# yacc2buss.net
KiCad netlist of a schematic drawn in EAGLE
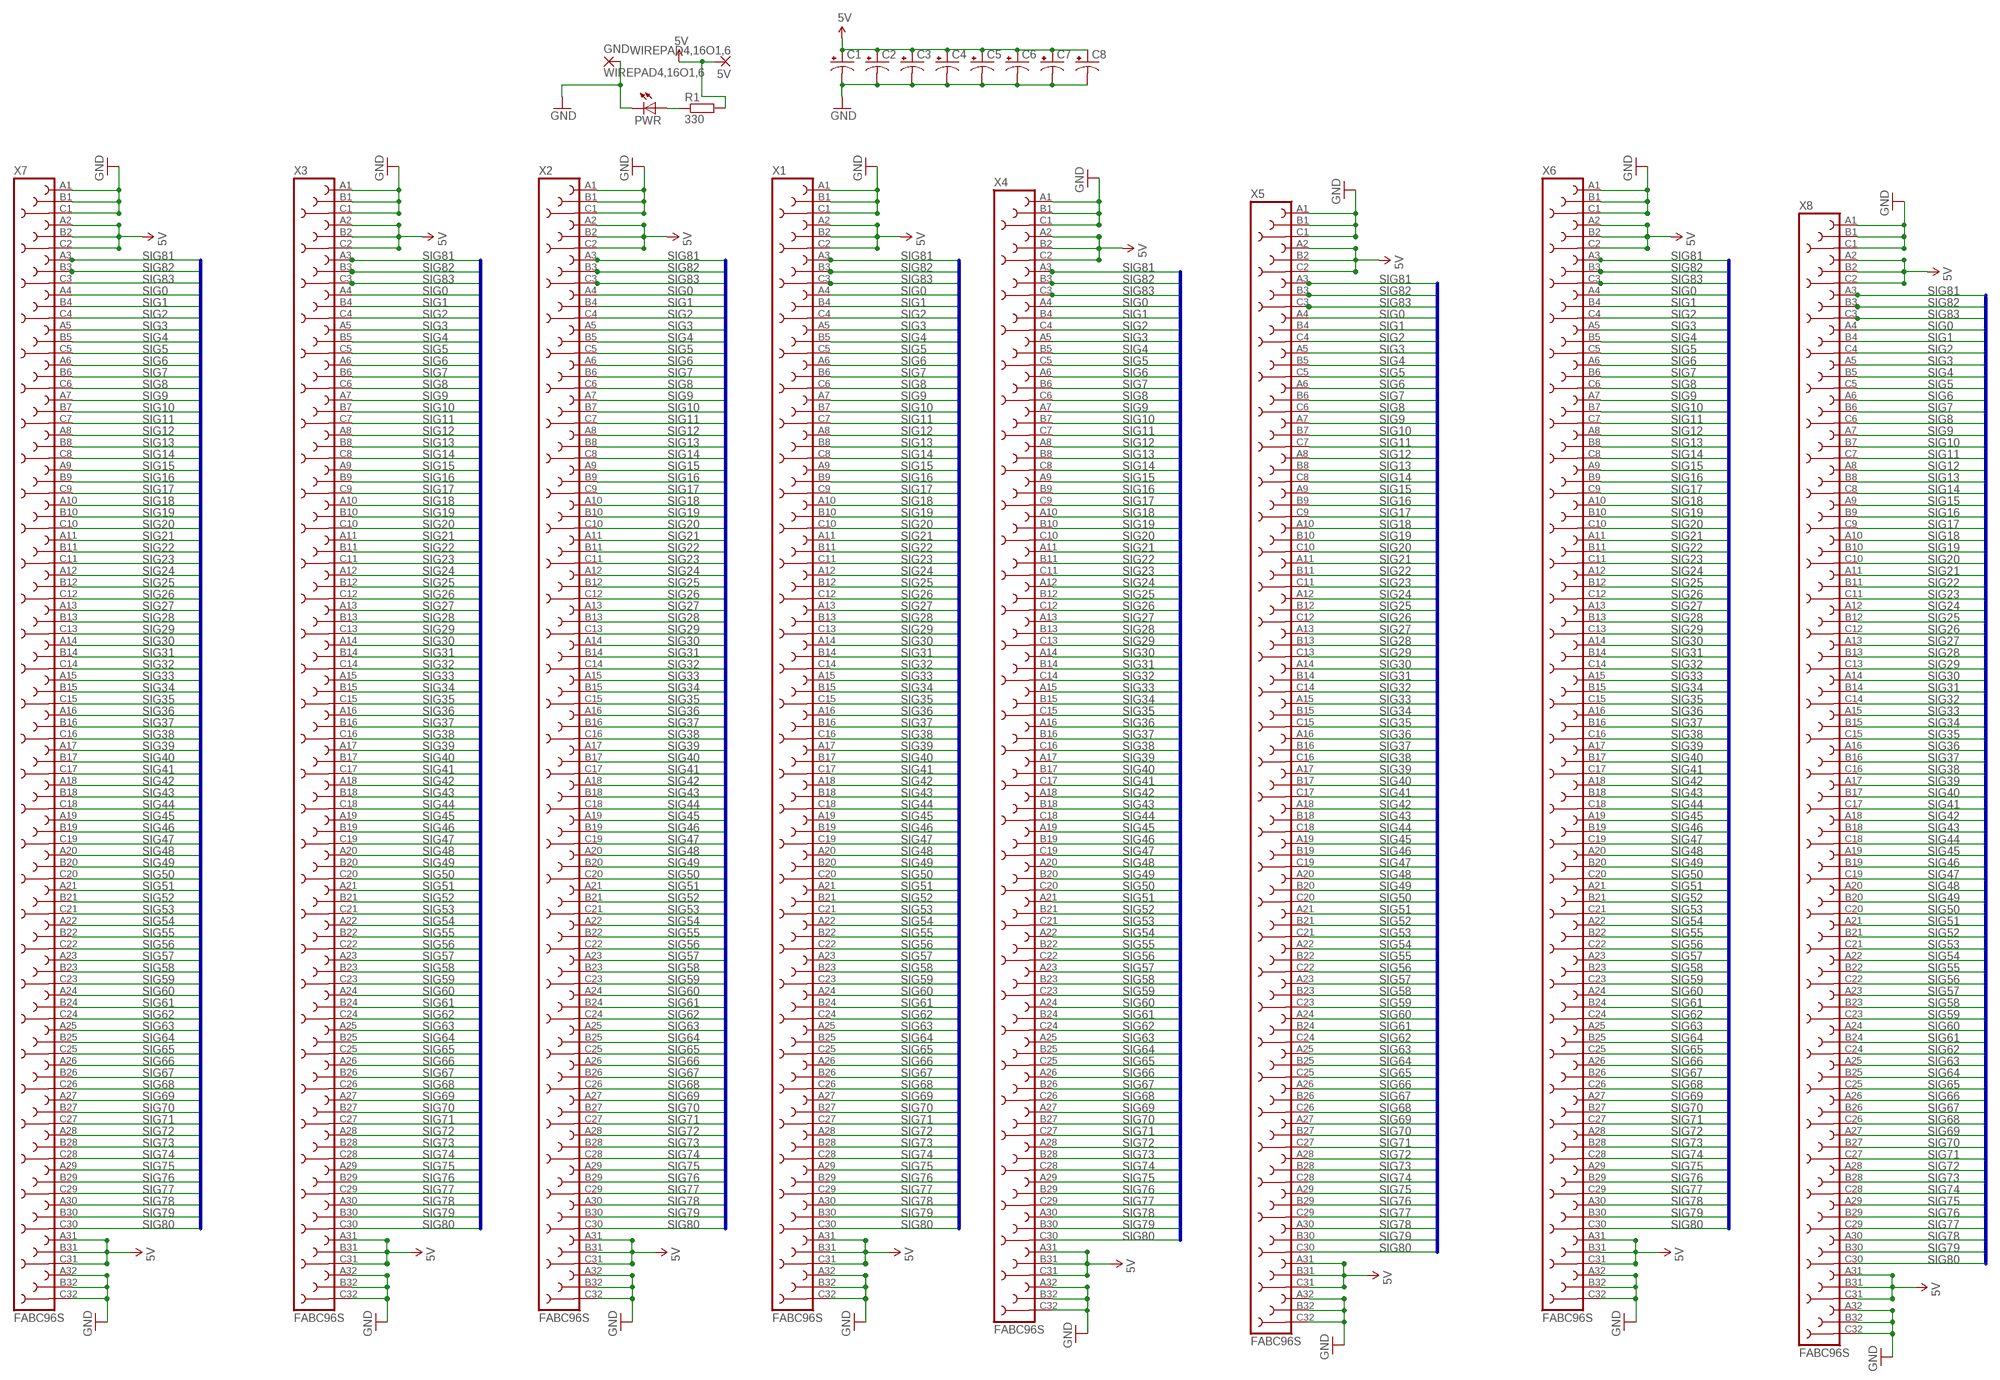
[diagram p0: schematic, sheet 1]

(export (version "E")
  (design (tool "Eeschema 10.0.6"))
  (components
    (comp (ref "5V")
      (value "WIREPAD4,16O1,6")
      (footprint "eagle-import:4,16O1,6")
      (libsource (lib "eagle-import") (part "WIREPAD4,16O1,6"))
    )
    (comp (ref "C1")
      (value "CPOL-USE5-6")
      (footprint "eagle-import:E5-6")
      (libsource (lib "eagle-import") (part "CPOL-USE5-6"))
    )
    (comp (ref "C2")
      (value "CPOL-USE5-6")
      (footprint "eagle-import:E5-6")
      (libsource (lib "eagle-import") (part "CPOL-USE5-6"))
    )
    (comp (ref "C3")
      (value "CPOL-USE5-6")
      (footprint "eagle-import:E5-6")
      (libsource (lib "eagle-import") (part "CPOL-USE5-6"))
    )
    (comp (ref "C4")
      (value "CPOL-USE5-6")
      (footprint "eagle-import:E5-6")
      (libsource (lib "eagle-import") (part "CPOL-USE5-6"))
    )
    (comp (ref "C5")
      (value "CPOL-USE5-6")
      (footprint "eagle-import:E5-6")
      (libsource (lib "eagle-import") (part "CPOL-USE5-6"))
    )
    (comp (ref "C6")
      (value "CPOL-USE5-6")
      (footprint "eagle-import:E5-6")
      (libsource (lib "eagle-import") (part "CPOL-USE5-6"))
    )
    (comp (ref "C7")
      (value "CPOL-USE5-6")
      (footprint "eagle-import:E5-6")
      (libsource (lib "eagle-import") (part "CPOL-USE5-6"))
    )
    (comp (ref "C8")
      (value "CPOL-USE5-6")
      (footprint "eagle-import:E5-6")
      (libsource (lib "eagle-import") (part "CPOL-USE5-6"))
    )
    (comp (ref "GND")
      (value "WIREPAD4,16O1,6")
      (footprint "eagle-import:4,16O1,6")
      (libsource (lib "eagle-import") (part "WIREPAD4,16O1,6"))
    )
    (comp (ref "PWR")
      (value "LED5MM")
      (footprint "eagle-import:LED5MM")
      (libsource (lib "eagle-import") (part "LED5MM"))
    )
    (comp (ref "R1")
      (value "330")
      (footprint "eagle-import:0207_10")
      (libsource (lib "eagle-import") (part "R0207/10"))
    )
    (comp (ref "X1")
      (value "FABC96S")
      (footprint "eagle-import:FABC96S")
      (libsource (lib "eagle-import") (part "FABC96S"))
    )
    (comp (ref "X2")
      (value "FABC96S")
      (footprint "eagle-import:FABC96S")
      (libsource (lib "eagle-import") (part "FABC96S"))
    )
    (comp (ref "X3")
      (value "FABC96S")
      (footprint "eagle-import:FABC96S")
      (libsource (lib "eagle-import") (part "FABC96S"))
    )
    (comp (ref "X4")
      (value "FABC96S")
      (footprint "eagle-import:FABC96S")
      (libsource (lib "eagle-import") (part "FABC96S"))
    )
    (comp (ref "X5")
      (value "FABC96S")
      (footprint "eagle-import:FABC96S")
      (libsource (lib "eagle-import") (part "FABC96S"))
    )
    (comp (ref "X6")
      (value "FABC96S")
      (footprint "eagle-import:FABC96S")
      (libsource (lib "eagle-import") (part "FABC96S"))
    )
    (comp (ref "X7")
      (value "FABC96S")
      (footprint "eagle-import:FABC96S")
      (libsource (lib "eagle-import") (part "FABC96S"))
    )
    (comp (ref "X8")
      (value "FABC96S")
      (footprint "eagle-import:FABC96S")
      (libsource (lib "eagle-import") (part "FABC96S"))
    )
  )
  (nets
    (net (code "1") (name "/SIG0") (class "Default")
      (node (ref "X1") (pin "A4") (pinfunction "A4_A4") (pintype "passive"))
      (node (ref "X2") (pin "A4") (pinfunction "A4_A4") (pintype "passive"))
      (node (ref "X3") (pin "A4") (pinfunction "A4_A4") (pintype "passive"))
      (node (ref "X4") (pin "A4") (pinfunction "A4_A4") (pintype "passive"))
      (node (ref "X5") (pin "A4") (pinfunction "A4_A4") (pintype "passive"))
      (node (ref "X6") (pin "A4") (pinfunction "A4_A4") (pintype "passive"))
      (node (ref "X7") (pin "A4") (pinfunction "A4_A4") (pintype "passive"))
      (node (ref "X8") (pin "A4") (pinfunction "A4_A4") (pintype "passive"))
    )
    (net (code "2") (name "/SIG1") (class "Default")
      (node (ref "X1") (pin "B4") (pinfunction "B4_B4") (pintype "passive"))
      (node (ref "X2") (pin "B4") (pinfunction "B4_B4") (pintype "passive"))
      (node (ref "X3") (pin "B4") (pinfunction "B4_B4") (pintype "passive"))
      (node (ref "X4") (pin "B4") (pinfunction "B4_B4") (pintype "passive"))
      (node (ref "X5") (pin "B4") (pinfunction "B4_B4") (pintype "passive"))
      (node (ref "X6") (pin "B4") (pinfunction "B4_B4") (pintype "passive"))
      (node (ref "X7") (pin "B4") (pinfunction "B4_B4") (pintype "passive"))
      (node (ref "X8") (pin "B4") (pinfunction "B4_B4") (pintype "passive"))
    )
    (net (code "3") (name "/SIG2") (class "Default")
      (node (ref "X1") (pin "C4") (pinfunction "C4_C4") (pintype "passive"))
      (node (ref "X2") (pin "C4") (pinfunction "C4_C4") (pintype "passive"))
      (node (ref "X3") (pin "C4") (pinfunction "C4_C4") (pintype "passive"))
      (node (ref "X4") (pin "C4") (pinfunction "C4_C4") (pintype "passive"))
      (node (ref "X5") (pin "C4") (pinfunction "C4_C4") (pintype "passive"))
      (node (ref "X6") (pin "C4") (pinfunction "C4_C4") (pintype "passive"))
      (node (ref "X7") (pin "C4") (pinfunction "C4_C4") (pintype "passive"))
      (node (ref "X8") (pin "C4") (pinfunction "C4_C4") (pintype "passive"))
    )
    (net (code "4") (name "/SIG3") (class "Default")
      (node (ref "X1") (pin "A5") (pinfunction "A5_A5") (pintype "passive"))
      (node (ref "X2") (pin "A5") (pinfunction "A5_A5") (pintype "passive"))
      (node (ref "X3") (pin "A5") (pinfunction "A5_A5") (pintype "passive"))
      (node (ref "X4") (pin "A5") (pinfunction "A5_A5") (pintype "passive"))
      (node (ref "X5") (pin "A5") (pinfunction "A5_A5") (pintype "passive"))
      (node (ref "X6") (pin "A5") (pinfunction "A5_A5") (pintype "passive"))
      (node (ref "X7") (pin "A5") (pinfunction "A5_A5") (pintype "passive"))
      (node (ref "X8") (pin "A5") (pinfunction "A5_A5") (pintype "passive"))
    )
    (net (code "5") (name "/SIG4") (class "Default")
      (node (ref "X1") (pin "B5") (pinfunction "B5_B5") (pintype "passive"))
      (node (ref "X2") (pin "B5") (pinfunction "B5_B5") (pintype "passive"))
      (node (ref "X3") (pin "B5") (pinfunction "B5_B5") (pintype "passive"))
      (node (ref "X4") (pin "B5") (pinfunction "B5_B5") (pintype "passive"))
      (node (ref "X5") (pin "B5") (pinfunction "B5_B5") (pintype "passive"))
      (node (ref "X6") (pin "B5") (pinfunction "B5_B5") (pintype "passive"))
      (node (ref "X7") (pin "B5") (pinfunction "B5_B5") (pintype "passive"))
      (node (ref "X8") (pin "B5") (pinfunction "B5_B5") (pintype "passive"))
    )
    (net (code "6") (name "/SIG5") (class "Default")
      (node (ref "X1") (pin "C5") (pinfunction "C5_C5") (pintype "passive"))
      (node (ref "X2") (pin "C5") (pinfunction "C5_C5") (pintype "passive"))
      (node (ref "X3") (pin "C5") (pinfunction "C5_C5") (pintype "passive"))
      (node (ref "X4") (pin "C5") (pinfunction "C5_C5") (pintype "passive"))
      (node (ref "X5") (pin "C5") (pinfunction "C5_C5") (pintype "passive"))
      (node (ref "X6") (pin "C5") (pinfunction "C5_C5") (pintype "passive"))
      (node (ref "X7") (pin "C5") (pinfunction "C5_C5") (pintype "passive"))
      (node (ref "X8") (pin "C5") (pinfunction "C5_C5") (pintype "passive"))
    )
    (net (code "7") (name "/SIG6") (class "Default")
      (node (ref "X1") (pin "A6") (pinfunction "A6_A6") (pintype "passive"))
      (node (ref "X2") (pin "A6") (pinfunction "A6_A6") (pintype "passive"))
      (node (ref "X3") (pin "A6") (pinfunction "A6_A6") (pintype "passive"))
      (node (ref "X4") (pin "A6") (pinfunction "A6_A6") (pintype "passive"))
      (node (ref "X5") (pin "A6") (pinfunction "A6_A6") (pintype "passive"))
      (node (ref "X6") (pin "A6") (pinfunction "A6_A6") (pintype "passive"))
      (node (ref "X7") (pin "A6") (pinfunction "A6_A6") (pintype "passive"))
      (node (ref "X8") (pin "A6") (pinfunction "A6_A6") (pintype "passive"))
    )
    (net (code "8") (name "/SIG7") (class "Default")
      (node (ref "X1") (pin "B6") (pinfunction "B6_B6") (pintype "passive"))
      (node (ref "X2") (pin "B6") (pinfunction "B6_B6") (pintype "passive"))
      (node (ref "X3") (pin "B6") (pinfunction "B6_B6") (pintype "passive"))
      (node (ref "X4") (pin "B6") (pinfunction "B6_B6") (pintype "passive"))
      (node (ref "X5") (pin "B6") (pinfunction "B6_B6") (pintype "passive"))
      (node (ref "X6") (pin "B6") (pinfunction "B6_B6") (pintype "passive"))
      (node (ref "X7") (pin "B6") (pinfunction "B6_B6") (pintype "passive"))
      (node (ref "X8") (pin "B6") (pinfunction "B6_B6") (pintype "passive"))
    )
    (net (code "9") (name "/SIG8") (class "Default")
      (node (ref "X1") (pin "C6") (pinfunction "C6_C6") (pintype "passive"))
      (node (ref "X2") (pin "C6") (pinfunction "C6_C6") (pintype "passive"))
      (node (ref "X3") (pin "C6") (pinfunction "C6_C6") (pintype "passive"))
      (node (ref "X4") (pin "C6") (pinfunction "C6_C6") (pintype "passive"))
      (node (ref "X5") (pin "C6") (pinfunction "C6_C6") (pintype "passive"))
      (node (ref "X6") (pin "C6") (pinfunction "C6_C6") (pintype "passive"))
      (node (ref "X7") (pin "C6") (pinfunction "C6_C6") (pintype "passive"))
      (node (ref "X8") (pin "C6") (pinfunction "C6_C6") (pintype "passive"))
    )
    (net (code "10") (name "/SIG9") (class "Default")
      (node (ref "X1") (pin "A7") (pinfunction "A7_A7") (pintype "passive"))
      (node (ref "X2") (pin "A7") (pinfunction "A7_A7") (pintype "passive"))
      (node (ref "X3") (pin "A7") (pinfunction "A7_A7") (pintype "passive"))
      (node (ref "X4") (pin "A7") (pinfunction "A7_A7") (pintype "passive"))
      (node (ref "X5") (pin "A7") (pinfunction "A7_A7") (pintype "passive"))
      (node (ref "X6") (pin "A7") (pinfunction "A7_A7") (pintype "passive"))
      (node (ref "X7") (pin "A7") (pinfunction "A7_A7") (pintype "passive"))
      (node (ref "X8") (pin "A7") (pinfunction "A7_A7") (pintype "passive"))
    )
    (net (code "11") (name "/SIG10") (class "Default")
      (node (ref "X1") (pin "B7") (pinfunction "B7_B7") (pintype "passive"))
      (node (ref "X2") (pin "B7") (pinfunction "B7_B7") (pintype "passive"))
      (node (ref "X3") (pin "B7") (pinfunction "B7_B7") (pintype "passive"))
      (node (ref "X4") (pin "B7") (pinfunction "B7_B7") (pintype "passive"))
      (node (ref "X5") (pin "B7") (pinfunction "B7_B7") (pintype "passive"))
      (node (ref "X6") (pin "B7") (pinfunction "B7_B7") (pintype "passive"))
      (node (ref "X7") (pin "B7") (pinfunction "B7_B7") (pintype "passive"))
      (node (ref "X8") (pin "B7") (pinfunction "B7_B7") (pintype "passive"))
    )
    (net (code "12") (name "/SIG11") (class "Default")
      (node (ref "X1") (pin "C7") (pinfunction "C7_C7") (pintype "passive"))
      (node (ref "X2") (pin "C7") (pinfunction "C7_C7") (pintype "passive"))
      (node (ref "X3") (pin "C7") (pinfunction "C7_C7") (pintype "passive"))
      (node (ref "X4") (pin "C7") (pinfunction "C7_C7") (pintype "passive"))
      (node (ref "X5") (pin "C7") (pinfunction "C7_C7") (pintype "passive"))
      (node (ref "X6") (pin "C7") (pinfunction "C7_C7") (pintype "passive"))
      (node (ref "X7") (pin "C7") (pinfunction "C7_C7") (pintype "passive"))
      (node (ref "X8") (pin "C7") (pinfunction "C7_C7") (pintype "passive"))
    )
    (net (code "13") (name "/SIG12") (class "Default")
      (node (ref "X1") (pin "A8") (pinfunction "A8_A8") (pintype "passive"))
      (node (ref "X2") (pin "A8") (pinfunction "A8_A8") (pintype "passive"))
      (node (ref "X3") (pin "A8") (pinfunction "A8_A8") (pintype "passive"))
      (node (ref "X4") (pin "A8") (pinfunction "A8_A8") (pintype "passive"))
      (node (ref "X5") (pin "A8") (pinfunction "A8_A8") (pintype "passive"))
      (node (ref "X6") (pin "A8") (pinfunction "A8_A8") (pintype "passive"))
      (node (ref "X7") (pin "A8") (pinfunction "A8_A8") (pintype "passive"))
      (node (ref "X8") (pin "A8") (pinfunction "A8_A8") (pintype "passive"))
    )
    (net (code "14") (name "/SIG13") (class "Default")
      (node (ref "X1") (pin "B8") (pinfunction "B8_B8") (pintype "passive"))
      (node (ref "X2") (pin "B8") (pinfunction "B8_B8") (pintype "passive"))
      (node (ref "X3") (pin "B8") (pinfunction "B8_B8") (pintype "passive"))
      (node (ref "X4") (pin "B8") (pinfunction "B8_B8") (pintype "passive"))
      (node (ref "X5") (pin "B8") (pinfunction "B8_B8") (pintype "passive"))
      (node (ref "X6") (pin "B8") (pinfunction "B8_B8") (pintype "passive"))
      (node (ref "X7") (pin "B8") (pinfunction "B8_B8") (pintype "passive"))
      (node (ref "X8") (pin "B8") (pinfunction "B8_B8") (pintype "passive"))
    )
    (net (code "15") (name "/SIG14") (class "Default")
      (node (ref "X1") (pin "C8") (pinfunction "C8_C8") (pintype "passive"))
      (node (ref "X2") (pin "C8") (pinfunction "C8_C8") (pintype "passive"))
      (node (ref "X3") (pin "C8") (pinfunction "C8_C8") (pintype "passive"))
      (node (ref "X4") (pin "C8") (pinfunction "C8_C8") (pintype "passive"))
      (node (ref "X5") (pin "C8") (pinfunction "C8_C8") (pintype "passive"))
      (node (ref "X6") (pin "C8") (pinfunction "C8_C8") (pintype "passive"))
      (node (ref "X7") (pin "C8") (pinfunction "C8_C8") (pintype "passive"))
      (node (ref "X8") (pin "C8") (pinfunction "C8_C8") (pintype "passive"))
    )
    (net (code "16") (name "/SIG15") (class "Default")
      (node (ref "X1") (pin "A9") (pinfunction "A9_A9") (pintype "passive"))
      (node (ref "X2") (pin "A9") (pinfunction "A9_A9") (pintype "passive"))
      (node (ref "X3") (pin "A9") (pinfunction "A9_A9") (pintype "passive"))
      (node (ref "X4") (pin "A9") (pinfunction "A9_A9") (pintype "passive"))
      (node (ref "X5") (pin "A9") (pinfunction "A9_A9") (pintype "passive"))
      (node (ref "X6") (pin "A9") (pinfunction "A9_A9") (pintype "passive"))
      (node (ref "X7") (pin "A9") (pinfunction "A9_A9") (pintype "passive"))
      (node (ref "X8") (pin "A9") (pinfunction "A9_A9") (pintype "passive"))
    )
    (net (code "17") (name "/SIG16") (class "Default")
      (node (ref "X1") (pin "B9") (pinfunction "B9_B9") (pintype "passive"))
      (node (ref "X2") (pin "B9") (pinfunction "B9_B9") (pintype "passive"))
      (node (ref "X3") (pin "B9") (pinfunction "B9_B9") (pintype "passive"))
      (node (ref "X4") (pin "B9") (pinfunction "B9_B9") (pintype "passive"))
      (node (ref "X5") (pin "B9") (pinfunction "B9_B9") (pintype "passive"))
      (node (ref "X6") (pin "B9") (pinfunction "B9_B9") (pintype "passive"))
      (node (ref "X7") (pin "B9") (pinfunction "B9_B9") (pintype "passive"))
      (node (ref "X8") (pin "B9") (pinfunction "B9_B9") (pintype "passive"))
    )
    (net (code "18") (name "/SIG17") (class "Default")
      (node (ref "X1") (pin "C9") (pinfunction "C9_C9") (pintype "passive"))
      (node (ref "X2") (pin "C9") (pinfunction "C9_C9") (pintype "passive"))
      (node (ref "X3") (pin "C9") (pinfunction "C9_C9") (pintype "passive"))
      (node (ref "X4") (pin "C9") (pinfunction "C9_C9") (pintype "passive"))
      (node (ref "X5") (pin "C9") (pinfunction "C9_C9") (pintype "passive"))
      (node (ref "X6") (pin "C9") (pinfunction "C9_C9") (pintype "passive"))
      (node (ref "X7") (pin "C9") (pinfunction "C9_C9") (pintype "passive"))
      (node (ref "X8") (pin "C9") (pinfunction "C9_C9") (pintype "passive"))
    )
    (net (code "19") (name "/SIG18") (class "Default")
      (node (ref "X1") (pin "A10") (pinfunction "A10_A10") (pintype "passive"))
      (node (ref "X2") (pin "A10") (pinfunction "A10_A10") (pintype "passive"))
      (node (ref "X3") (pin "A10") (pinfunction "A10_A10") (pintype "passive"))
      (node (ref "X4") (pin "A10") (pinfunction "A10_A10") (pintype "passive"))
      (node (ref "X5") (pin "A10") (pinfunction "A10_A10") (pintype "passive"))
      (node (ref "X6") (pin "A10") (pinfunction "A10_A10") (pintype "passive"))
      (node (ref "X7") (pin "A10") (pinfunction "A10_A10") (pintype "passive"))
      (node (ref "X8") (pin "A10") (pinfunction "A10_A10") (pintype "passive"))
    )
    (net (code "20") (name "/SIG19") (class "Default")
      (node (ref "X1") (pin "B10") (pinfunction "B10_B10") (pintype "passive"))
      (node (ref "X2") (pin "B10") (pinfunction "B10_B10") (pintype "passive"))
      (node (ref "X3") (pin "B10") (pinfunction "B10_B10") (pintype "passive"))
      (node (ref "X4") (pin "B10") (pinfunction "B10_B10") (pintype "passive"))
      (node (ref "X5") (pin "B10") (pinfunction "B10_B10") (pintype "passive"))
      (node (ref "X6") (pin "B10") (pinfunction "B10_B10") (pintype "passive"))
      (node (ref "X7") (pin "B10") (pinfunction "B10_B10") (pintype "passive"))
      (node (ref "X8") (pin "B10") (pinfunction "B10_B10") (pintype "passive"))
    )
    (net (code "21") (name "/SIG20") (class "Default")
      (node (ref "X1") (pin "C10") (pinfunction "C10_C10") (pintype "passive"))
      (node (ref "X2") (pin "C10") (pinfunction "C10_C10") (pintype "passive"))
      (node (ref "X3") (pin "C10") (pinfunction "C10_C10") (pintype "passive"))
      (node (ref "X4") (pin "C10") (pinfunction "C10_C10") (pintype "passive"))
      (node (ref "X5") (pin "C10") (pinfunction "C10_C10") (pintype "passive"))
      (node (ref "X6") (pin "C10") (pinfunction "C10_C10") (pintype "passive"))
      (node (ref "X7") (pin "C10") (pinfunction "C10_C10") (pintype "passive"))
      (node (ref "X8") (pin "C10") (pinfunction "C10_C10") (pintype "passive"))
    )
    (net (code "22") (name "/SIG21") (class "Default")
      (node (ref "X1") (pin "A11") (pinfunction "A11_A11") (pintype "passive"))
      (node (ref "X2") (pin "A11") (pinfunction "A11_A11") (pintype "passive"))
      (node (ref "X3") (pin "A11") (pinfunction "A11_A11") (pintype "passive"))
      (node (ref "X4") (pin "A11") (pinfunction "A11_A11") (pintype "passive"))
      (node (ref "X5") (pin "A11") (pinfunction "A11_A11") (pintype "passive"))
      (node (ref "X6") (pin "A11") (pinfunction "A11_A11") (pintype "passive"))
      (node (ref "X7") (pin "A11") (pinfunction "A11_A11") (pintype "passive"))
      (node (ref "X8") (pin "A11") (pinfunction "A11_A11") (pintype "passive"))
    )
    (net (code "23") (name "/SIG22") (class "Default")
      (node (ref "X1") (pin "B11") (pinfunction "B11_B11") (pintype "passive"))
      (node (ref "X2") (pin "B11") (pinfunction "B11_B11") (pintype "passive"))
      (node (ref "X3") (pin "B11") (pinfunction "B11_B11") (pintype "passive"))
      (node (ref "X4") (pin "B11") (pinfunction "B11_B11") (pintype "passive"))
      (node (ref "X5") (pin "B11") (pinfunction "B11_B11") (pintype "passive"))
      (node (ref "X6") (pin "B11") (pinfunction "B11_B11") (pintype "passive"))
      (node (ref "X7") (pin "B11") (pinfunction "B11_B11") (pintype "passive"))
      (node (ref "X8") (pin "B11") (pinfunction "B11_B11") (pintype "passive"))
    )
    (net (code "24") (name "/SIG23") (class "Default")
      (node (ref "X1") (pin "C11") (pinfunction "C11_C11") (pintype "passive"))
      (node (ref "X2") (pin "C11") (pinfunction "C11_C11") (pintype "passive"))
      (node (ref "X3") (pin "C11") (pinfunction "C11_C11") (pintype "passive"))
      (node (ref "X4") (pin "C11") (pinfunction "C11_C11") (pintype "passive"))
      (node (ref "X5") (pin "C11") (pinfunction "C11_C11") (pintype "passive"))
      (node (ref "X6") (pin "C11") (pinfunction "C11_C11") (pintype "passive"))
      (node (ref "X7") (pin "C11") (pinfunction "C11_C11") (pintype "passive"))
      (node (ref "X8") (pin "C11") (pinfunction "C11_C11") (pintype "passive"))
    )
    (net (code "25") (name "/SIG24") (class "Default")
      (node (ref "X1") (pin "A12") (pinfunction "A12_A12") (pintype "passive"))
      (node (ref "X2") (pin "A12") (pinfunction "A12_A12") (pintype "passive"))
      (node (ref "X3") (pin "A12") (pinfunction "A12_A12") (pintype "passive"))
      (node (ref "X4") (pin "A12") (pinfunction "A12_A12") (pintype "passive"))
      (node (ref "X5") (pin "A12") (pinfunction "A12_A12") (pintype "passive"))
      (node (ref "X6") (pin "A12") (pinfunction "A12_A12") (pintype "passive"))
      (node (ref "X7") (pin "A12") (pinfunction "A12_A12") (pintype "passive"))
      (node (ref "X8") (pin "A12") (pinfunction "A12_A12") (pintype "passive"))
    )
    (net (code "26") (name "/SIG25") (class "Default")
      (node (ref "X1") (pin "B12") (pinfunction "B12_B12") (pintype "passive"))
      (node (ref "X2") (pin "B12") (pinfunction "B12_B12") (pintype "passive"))
      (node (ref "X3") (pin "B12") (pinfunction "B12_B12") (pintype "passive"))
      (node (ref "X4") (pin "B12") (pinfunction "B12_B12") (pintype "passive"))
      (node (ref "X5") (pin "B12") (pinfunction "B12_B12") (pintype "passive"))
      (node (ref "X6") (pin "B12") (pinfunction "B12_B12") (pintype "passive"))
      (node (ref "X7") (pin "B12") (pinfunction "B12_B12") (pintype "passive"))
      (node (ref "X8") (pin "B12") (pinfunction "B12_B12") (pintype "passive"))
    )
    (net (code "27") (name "/SIG26") (class "Default")
      (node (ref "X1") (pin "C12") (pinfunction "C12_C12") (pintype "passive"))
      (node (ref "X2") (pin "C12") (pinfunction "C12_C12") (pintype "passive"))
      (node (ref "X3") (pin "C12") (pinfunction "C12_C12") (pintype "passive"))
      (node (ref "X4") (pin "C12") (pinfunction "C12_C12") (pintype "passive"))
      (node (ref "X5") (pin "C12") (pinfunction "C12_C12") (pintype "passive"))
      (node (ref "X6") (pin "C12") (pinfunction "C12_C12") (pintype "passive"))
      (node (ref "X7") (pin "C12") (pinfunction "C12_C12") (pintype "passive"))
      (node (ref "X8") (pin "C12") (pinfunction "C12_C12") (pintype "passive"))
    )
    (net (code "28") (name "/SIG27") (class "Default")
      (node (ref "X1") (pin "A13") (pinfunction "A13_A13") (pintype "passive"))
      (node (ref "X2") (pin "A13") (pinfunction "A13_A13") (pintype "passive"))
      (node (ref "X3") (pin "A13") (pinfunction "A13_A13") (pintype "passive"))
      (node (ref "X4") (pin "A13") (pinfunction "A13_A13") (pintype "passive"))
      (node (ref "X5") (pin "A13") (pinfunction "A13_A13") (pintype "passive"))
      (node (ref "X6") (pin "A13") (pinfunction "A13_A13") (pintype "passive"))
      (node (ref "X7") (pin "A13") (pinfunction "A13_A13") (pintype "passive"))
      (node (ref "X8") (pin "A13") (pinfunction "A13_A13") (pintype "passive"))
    )
    (net (code "29") (name "/SIG28") (class "Default")
      (node (ref "X1") (pin "B13") (pinfunction "B13_B13") (pintype "passive"))
      (node (ref "X2") (pin "B13") (pinfunction "B13_B13") (pintype "passive"))
      (node (ref "X3") (pin "B13") (pinfunction "B13_B13") (pintype "passive"))
      (node (ref "X4") (pin "B13") (pinfunction "B13_B13") (pintype "passive"))
      (node (ref "X5") (pin "B13") (pinfunction "B13_B13") (pintype "passive"))
      (node (ref "X6") (pin "B13") (pinfunction "B13_B13") (pintype "passive"))
      (node (ref "X7") (pin "B13") (pinfunction "B13_B13") (pintype "passive"))
      (node (ref "X8") (pin "B13") (pinfunction "B13_B13") (pintype "passive"))
    )
    (net (code "30") (name "/SIG29") (class "Default")
      (node (ref "X1") (pin "C13") (pinfunction "C13_C13") (pintype "passive"))
      (node (ref "X2") (pin "C13") (pinfunction "C13_C13") (pintype "passive"))
      (node (ref "X3") (pin "C13") (pinfunction "C13_C13") (pintype "passive"))
      (node (ref "X4") (pin "C13") (pinfunction "C13_C13") (pintype "passive"))
      (node (ref "X5") (pin "C13") (pinfunction "C13_C13") (pintype "passive"))
      (node (ref "X6") (pin "C13") (pinfunction "C13_C13") (pintype "passive"))
      (node (ref "X7") (pin "C13") (pinfunction "C13_C13") (pintype "passive"))
      (node (ref "X8") (pin "C13") (pinfunction "C13_C13") (pintype "passive"))
    )
    (net (code "31") (name "/SIG30") (class "Default")
      (node (ref "X1") (pin "A14") (pinfunction "A14_A14") (pintype "passive"))
      (node (ref "X2") (pin "A14") (pinfunction "A14_A14") (pintype "passive"))
      (node (ref "X3") (pin "A14") (pinfunction "A14_A14") (pintype "passive"))
      (node (ref "X4") (pin "A14") (pinfunction "A14_A14") (pintype "passive"))
      (node (ref "X5") (pin "A14") (pinfunction "A14_A14") (pintype "passive"))
      (node (ref "X6") (pin "A14") (pinfunction "A14_A14") (pintype "passive"))
      (node (ref "X7") (pin "A14") (pinfunction "A14_A14") (pintype "passive"))
      (node (ref "X8") (pin "A14") (pinfunction "A14_A14") (pintype "passive"))
    )
    (net (code "32") (name "/SIG31") (class "Default")
      (node (ref "X1") (pin "B14") (pinfunction "B14_B14") (pintype "passive"))
      (node (ref "X2") (pin "B14") (pinfunction "B14_B14") (pintype "passive"))
      (node (ref "X3") (pin "B14") (pinfunction "B14_B14") (pintype "passive"))
      (node (ref "X4") (pin "B14") (pinfunction "B14_B14") (pintype "passive"))
      (node (ref "X5") (pin "B14") (pinfunction "B14_B14") (pintype "passive"))
      (node (ref "X6") (pin "B14") (pinfunction "B14_B14") (pintype "passive"))
      (node (ref "X7") (pin "B14") (pinfunction "B14_B14") (pintype "passive"))
      (node (ref "X8") (pin "B14") (pinfunction "B14_B14") (pintype "passive"))
    )
    (net (code "33") (name "/SIG32") (class "Default")
      (node (ref "X1") (pin "C14") (pinfunction "C14_C14") (pintype "passive"))
      (node (ref "X2") (pin "C14") (pinfunction "C14_C14") (pintype "passive"))
      (node (ref "X3") (pin "C14") (pinfunction "C14_C14") (pintype "passive"))
      (node (ref "X4") (pin "C14") (pinfunction "C14_C14") (pintype "passive"))
      (node (ref "X5") (pin "C14") (pinfunction "C14_C14") (pintype "passive"))
      (node (ref "X6") (pin "C14") (pinfunction "C14_C14") (pintype "passive"))
      (node (ref "X7") (pin "C14") (pinfunction "C14_C14") (pintype "passive"))
      (node (ref "X8") (pin "C14") (pinfunction "C14_C14") (pintype "passive"))
    )
    (net (code "34") (name "/SIG33") (class "Default")
      (node (ref "X1") (pin "A15") (pinfunction "A15_A15") (pintype "passive"))
      (node (ref "X2") (pin "A15") (pinfunction "A15_A15") (pintype "passive"))
      (node (ref "X3") (pin "A15") (pinfunction "A15_A15") (pintype "passive"))
      (node (ref "X4") (pin "A15") (pinfunction "A15_A15") (pintype "passive"))
      (node (ref "X5") (pin "A15") (pinfunction "A15_A15") (pintype "passive"))
      (node (ref "X6") (pin "A15") (pinfunction "A15_A15") (pintype "passive"))
      (node (ref "X7") (pin "A15") (pinfunction "A15_A15") (pintype "passive"))
      (node (ref "X8") (pin "A15") (pinfunction "A15_A15") (pintype "passive"))
    )
    (net (code "35") (name "/SIG34") (class "Default")
      (node (ref "X1") (pin "B15") (pinfunction "B15_B15") (pintype "passive"))
      (node (ref "X2") (pin "B15") (pinfunction "B15_B15") (pintype "passive"))
      (node (ref "X3") (pin "B15") (pinfunction "B15_B15") (pintype "passive"))
      (node (ref "X4") (pin "B15") (pinfunction "B15_B15") (pintype "passive"))
      (node (ref "X5") (pin "B15") (pinfunction "B15_B15") (pintype "passive"))
      (node (ref "X6") (pin "B15") (pinfunction "B15_B15") (pintype "passive"))
      (node (ref "X7") (pin "B15") (pinfunction "B15_B15") (pintype "passive"))
      (node (ref "X8") (pin "B15") (pinfunction "B15_B15") (pintype "passive"))
    )
    (net (code "36") (name "/SIG35") (class "Default")
      (node (ref "X1") (pin "C15") (pinfunction "C15_C15") (pintype "passive"))
      (node (ref "X2") (pin "C15") (pinfunction "C15_C15") (pintype "passive"))
      (node (ref "X3") (pin "C15") (pinfunction "C15_C15") (pintype "passive"))
      (node (ref "X4") (pin "C15") (pinfunction "C15_C15") (pintype "passive"))
      (node (ref "X5") (pin "C15") (pinfunction "C15_C15") (pintype "passive"))
      (node (ref "X6") (pin "C15") (pinfunction "C15_C15") (pintype "passive"))
      (node (ref "X7") (pin "C15") (pinfunction "C15_C15") (pintype "passive"))
      (node (ref "X8") (pin "C15") (pinfunction "C15_C15") (pintype "passive"))
    )
    (net (code "37") (name "/SIG36") (class "Default")
      (node (ref "X1") (pin "A16") (pinfunction "A16_A16") (pintype "passive"))
      (node (ref "X2") (pin "A16") (pinfunction "A16_A16") (pintype "passive"))
      (node (ref "X3") (pin "A16") (pinfunction "A16_A16") (pintype "passive"))
      (node (ref "X4") (pin "A16") (pinfunction "A16_A16") (pintype "passive"))
      (node (ref "X5") (pin "A16") (pinfunction "A16_A16") (pintype "passive"))
      (node (ref "X6") (pin "A16") (pinfunction "A16_A16") (pintype "passive"))
      (node (ref "X7") (pin "A16") (pinfunction "A16_A16") (pintype "passive"))
      (node (ref "X8") (pin "A16") (pinfunction "A16_A16") (pintype "passive"))
    )
    (net (code "38") (name "/SIG37") (class "Default")
      (node (ref "X1") (pin "B16") (pinfunction "B16_B16") (pintype "passive"))
      (node (ref "X2") (pin "B16") (pinfunction "B16_B16") (pintype "passive"))
      (node (ref "X3") (pin "B16") (pinfunction "B16_B16") (pintype "passive"))
      (node (ref "X4") (pin "B16") (pinfunction "B16_B16") (pintype "passive"))
      (node (ref "X5") (pin "B16") (pinfunction "B16_B16") (pintype "passive"))
      (node (ref "X6") (pin "B16") (pinfunction "B16_B16") (pintype "passive"))
      (node (ref "X7") (pin "B16") (pinfunction "B16_B16") (pintype "passive"))
      (node (ref "X8") (pin "B16") (pinfunction "B16_B16") (pintype "passive"))
    )
    (net (code "39") (name "/SIG38") (class "Default")
      (node (ref "X1") (pin "C16") (pinfunction "C16_C16") (pintype "passive"))
      (node (ref "X2") (pin "C16") (pinfunction "C16_C16") (pintype "passive"))
      (node (ref "X3") (pin "C16") (pinfunction "C16_C16") (pintype "passive"))
      (node (ref "X4") (pin "C16") (pinfunction "C16_C16") (pintype "passive"))
      (node (ref "X5") (pin "C16") (pinfunction "C16_C16") (pintype "passive"))
      (node (ref "X6") (pin "C16") (pinfunction "C16_C16") (pintype "passive"))
      (node (ref "X7") (pin "C16") (pinfunction "C16_C16") (pintype "passive"))
      (node (ref "X8") (pin "C16") (pinfunction "C16_C16") (pintype "passive"))
    )
    (net (code "40") (name "/SIG39") (class "Default")
      (node (ref "X1") (pin "A17") (pinfunction "A17_A17") (pintype "passive"))
      (node (ref "X2") (pin "A17") (pinfunction "A17_A17") (pintype "passive"))
      (node (ref "X3") (pin "A17") (pinfunction "A17_A17") (pintype "passive"))
      (node (ref "X4") (pin "A17") (pinfunction "A17_A17") (pintype "passive"))
      (node (ref "X5") (pin "A17") (pinfunction "A17_A17") (pintype "passive"))
      (node (ref "X6") (pin "A17") (pinfunction "A17_A17") (pintype "passive"))
      (node (ref "X7") (pin "A17") (pinfunction "A17_A17") (pintype "passive"))
      (node (ref "X8") (pin "A17") (pinfunction "A17_A17") (pintype "passive"))
    )
    (net (code "41") (name "/SIG40") (class "Default")
      (node (ref "X1") (pin "B17") (pinfunction "B17_B17") (pintype "passive"))
      (node (ref "X2") (pin "B17") (pinfunction "B17_B17") (pintype "passive"))
      (node (ref "X3") (pin "B17") (pinfunction "B17_B17") (pintype "passive"))
      (node (ref "X4") (pin "B17") (pinfunction "B17_B17") (pintype "passive"))
      (node (ref "X5") (pin "B17") (pinfunction "B17_B17") (pintype "passive"))
      (node (ref "X6") (pin "B17") (pinfunction "B17_B17") (pintype "passive"))
      (node (ref "X7") (pin "B17") (pinfunction "B17_B17") (pintype "passive"))
      (node (ref "X8") (pin "B17") (pinfunction "B17_B17") (pintype "passive"))
    )
    (net (code "42") (name "/SIG41") (class "Default")
      (node (ref "X1") (pin "C17") (pinfunction "C17_C17") (pintype "passive"))
      (node (ref "X2") (pin "C17") (pinfunction "C17_C17") (pintype "passive"))
      (node (ref "X3") (pin "C17") (pinfunction "C17_C17") (pintype "passive"))
      (node (ref "X4") (pin "C17") (pinfunction "C17_C17") (pintype "passive"))
      (node (ref "X5") (pin "C17") (pinfunction "C17_C17") (pintype "passive"))
      (node (ref "X6") (pin "C17") (pinfunction "C17_C17") (pintype "passive"))
      (node (ref "X7") (pin "C17") (pinfunction "C17_C17") (pintype "passive"))
      (node (ref "X8") (pin "C17") (pinfunction "C17_C17") (pintype "passive"))
    )
    (net (code "43") (name "/SIG42") (class "Default")
      (node (ref "X1") (pin "A18") (pinfunction "A18_A18") (pintype "passive"))
      (node (ref "X2") (pin "A18") (pinfunction "A18_A18") (pintype "passive"))
      (node (ref "X3") (pin "A18") (pinfunction "A18_A18") (pintype "passive"))
      (node (ref "X4") (pin "A18") (pinfunction "A18_A18") (pintype "passive"))
      (node (ref "X5") (pin "A18") (pinfunction "A18_A18") (pintype "passive"))
      (node (ref "X6") (pin "A18") (pinfunction "A18_A18") (pintype "passive"))
      (node (ref "X7") (pin "A18") (pinfunction "A18_A18") (pintype "passive"))
      (node (ref "X8") (pin "A18") (pinfunction "A18_A18") (pintype "passive"))
    )
    (net (code "44") (name "/SIG43") (class "Default")
      (node (ref "X1") (pin "B18") (pinfunction "B18_B18") (pintype "passive"))
      (node (ref "X2") (pin "B18") (pinfunction "B18_B18") (pintype "passive"))
      (node (ref "X3") (pin "B18") (pinfunction "B18_B18") (pintype "passive"))
      (node (ref "X4") (pin "B18") (pinfunction "B18_B18") (pintype "passive"))
      (node (ref "X5") (pin "B18") (pinfunction "B18_B18") (pintype "passive"))
      (node (ref "X6") (pin "B18") (pinfunction "B18_B18") (pintype "passive"))
      (node (ref "X7") (pin "B18") (pinfunction "B18_B18") (pintype "passive"))
      (node (ref "X8") (pin "B18") (pinfunction "B18_B18") (pintype "passive"))
    )
    (net (code "45") (name "/SIG44") (class "Default")
      (node (ref "X1") (pin "C18") (pinfunction "C18_C18") (pintype "passive"))
      (node (ref "X2") (pin "C18") (pinfunction "C18_C18") (pintype "passive"))
      (node (ref "X3") (pin "C18") (pinfunction "C18_C18") (pintype "passive"))
      (node (ref "X4") (pin "C18") (pinfunction "C18_C18") (pintype "passive"))
      (node (ref "X5") (pin "C18") (pinfunction "C18_C18") (pintype "passive"))
      (node (ref "X6") (pin "C18") (pinfunction "C18_C18") (pintype "passive"))
      (node (ref "X7") (pin "C18") (pinfunction "C18_C18") (pintype "passive"))
      (node (ref "X8") (pin "C18") (pinfunction "C18_C18") (pintype "passive"))
    )
    (net (code "46") (name "/SIG45") (class "Default")
      (node (ref "X1") (pin "A19") (pinfunction "A19_A19") (pintype "passive"))
      (node (ref "X2") (pin "A19") (pinfunction "A19_A19") (pintype "passive"))
      (node (ref "X3") (pin "A19") (pinfunction "A19_A19") (pintype "passive"))
      (node (ref "X4") (pin "A19") (pinfunction "A19_A19") (pintype "passive"))
      (node (ref "X5") (pin "A19") (pinfunction "A19_A19") (pintype "passive"))
      (node (ref "X6") (pin "A19") (pinfunction "A19_A19") (pintype "passive"))
      (node (ref "X7") (pin "A19") (pinfunction "A19_A19") (pintype "passive"))
      (node (ref "X8") (pin "A19") (pinfunction "A19_A19") (pintype "passive"))
    )
    (net (code "47") (name "/SIG46") (class "Default")
      (node (ref "X1") (pin "B19") (pinfunction "B19_B19") (pintype "passive"))
      (node (ref "X2") (pin "B19") (pinfunction "B19_B19") (pintype "passive"))
      (node (ref "X3") (pin "B19") (pinfunction "B19_B19") (pintype "passive"))
      (node (ref "X4") (pin "B19") (pinfunction "B19_B19") (pintype "passive"))
      (node (ref "X5") (pin "B19") (pinfunction "B19_B19") (pintype "passive"))
      (node (ref "X6") (pin "B19") (pinfunction "B19_B19") (pintype "passive"))
      (node (ref "X7") (pin "B19") (pinfunction "B19_B19") (pintype "passive"))
      (node (ref "X8") (pin "B19") (pinfunction "B19_B19") (pintype "passive"))
    )
    (net (code "48") (name "/SIG47") (class "Default")
      (node (ref "X1") (pin "C19") (pinfunction "C19_C19") (pintype "passive"))
      (node (ref "X2") (pin "C19") (pinfunction "C19_C19") (pintype "passive"))
      (node (ref "X3") (pin "C19") (pinfunction "C19_C19") (pintype "passive"))
      (node (ref "X4") (pin "C19") (pinfunction "C19_C19") (pintype "passive"))
      (node (ref "X5") (pin "C19") (pinfunction "C19_C19") (pintype "passive"))
      (node (ref "X6") (pin "C19") (pinfunction "C19_C19") (pintype "passive"))
      (node (ref "X7") (pin "C19") (pinfunction "C19_C19") (pintype "passive"))
      (node (ref "X8") (pin "C19") (pinfunction "C19_C19") (pintype "passive"))
    )
    (net (code "49") (name "/SIG48") (class "Default")
      (node (ref "X1") (pin "A20") (pinfunction "A20_A20") (pintype "passive"))
      (node (ref "X2") (pin "A20") (pinfunction "A20_A20") (pintype "passive"))
      (node (ref "X3") (pin "A20") (pinfunction "A20_A20") (pintype "passive"))
      (node (ref "X4") (pin "A20") (pinfunction "A20_A20") (pintype "passive"))
      (node (ref "X5") (pin "A20") (pinfunction "A20_A20") (pintype "passive"))
      (node (ref "X6") (pin "A20") (pinfunction "A20_A20") (pintype "passive"))
      (node (ref "X7") (pin "A20") (pinfunction "A20_A20") (pintype "passive"))
      (node (ref "X8") (pin "A20") (pinfunction "A20_A20") (pintype "passive"))
    )
    (net (code "50") (name "/SIG49") (class "Default")
      (node (ref "X1") (pin "B20") (pinfunction "B20_B20") (pintype "passive"))
      (node (ref "X2") (pin "B20") (pinfunction "B20_B20") (pintype "passive"))
      (node (ref "X3") (pin "B20") (pinfunction "B20_B20") (pintype "passive"))
      (node (ref "X4") (pin "B20") (pinfunction "B20_B20") (pintype "passive"))
      (node (ref "X5") (pin "B20") (pinfunction "B20_B20") (pintype "passive"))
      (node (ref "X6") (pin "B20") (pinfunction "B20_B20") (pintype "passive"))
      (node (ref "X7") (pin "B20") (pinfunction "B20_B20") (pintype "passive"))
      (node (ref "X8") (pin "B20") (pinfunction "B20_B20") (pintype "passive"))
    )
    (net (code "51") (name "/SIG50") (class "Default")
      (node (ref "X1") (pin "C20") (pinfunction "C20_C20") (pintype "passive"))
      (node (ref "X2") (pin "C20") (pinfunction "C20_C20") (pintype "passive"))
      (node (ref "X3") (pin "C20") (pinfunction "C20_C20") (pintype "passive"))
      (node (ref "X4") (pin "C20") (pinfunction "C20_C20") (pintype "passive"))
      (node (ref "X5") (pin "C20") (pinfunction "C20_C20") (pintype "passive"))
      (node (ref "X6") (pin "C20") (pinfunction "C20_C20") (pintype "passive"))
      (node (ref "X7") (pin "C20") (pinfunction "C20_C20") (pintype "passive"))
      (node (ref "X8") (pin "C20") (pinfunction "C20_C20") (pintype "passive"))
    )
    (net (code "52") (name "/SIG51") (class "Default")
      (node (ref "X1") (pin "A21") (pinfunction "A21_A21") (pintype "passive"))
      (node (ref "X2") (pin "A21") (pinfunction "A21_A21") (pintype "passive"))
      (node (ref "X3") (pin "A21") (pinfunction "A21_A21") (pintype "passive"))
      (node (ref "X4") (pin "A21") (pinfunction "A21_A21") (pintype "passive"))
      (node (ref "X5") (pin "A21") (pinfunction "A21_A21") (pintype "passive"))
      (node (ref "X6") (pin "A21") (pinfunction "A21_A21") (pintype "passive"))
      (node (ref "X7") (pin "A21") (pinfunction "A21_A21") (pintype "passive"))
      (node (ref "X8") (pin "A21") (pinfunction "A21_A21") (pintype "passive"))
    )
    (net (code "53") (name "/SIG52") (class "Default")
      (node (ref "X1") (pin "B21") (pinfunction "B21_B21") (pintype "passive"))
      (node (ref "X2") (pin "B21") (pinfunction "B21_B21") (pintype "passive"))
      (node (ref "X3") (pin "B21") (pinfunction "B21_B21") (pintype "passive"))
      (node (ref "X4") (pin "B21") (pinfunction "B21_B21") (pintype "passive"))
      (node (ref "X5") (pin "B21") (pinfunction "B21_B21") (pintype "passive"))
      (node (ref "X6") (pin "B21") (pinfunction "B21_B21") (pintype "passive"))
      (node (ref "X7") (pin "B21") (pinfunction "B21_B21") (pintype "passive"))
      (node (ref "X8") (pin "B21") (pinfunction "B21_B21") (pintype "passive"))
    )
    (net (code "54") (name "/SIG53") (class "Default")
      (node (ref "X1") (pin "C21") (pinfunction "C21_C21") (pintype "passive"))
      (node (ref "X2") (pin "C21") (pinfunction "C21_C21") (pintype "passive"))
      (node (ref "X3") (pin "C21") (pinfunction "C21_C21") (pintype "passive"))
      (node (ref "X4") (pin "C21") (pinfunction "C21_C21") (pintype "passive"))
      (node (ref "X5") (pin "C21") (pinfunction "C21_C21") (pintype "passive"))
      (node (ref "X6") (pin "C21") (pinfunction "C21_C21") (pintype "passive"))
      (node (ref "X7") (pin "C21") (pinfunction "C21_C21") (pintype "passive"))
      (node (ref "X8") (pin "C21") (pinfunction "C21_C21") (pintype "passive"))
    )
    (net (code "55") (name "/SIG54") (class "Default")
      (node (ref "X1") (pin "A22") (pinfunction "A22_A22") (pintype "passive"))
      (node (ref "X2") (pin "A22") (pinfunction "A22_A22") (pintype "passive"))
      (node (ref "X3") (pin "A22") (pinfunction "A22_A22") (pintype "passive"))
      (node (ref "X4") (pin "A22") (pinfunction "A22_A22") (pintype "passive"))
      (node (ref "X5") (pin "A22") (pinfunction "A22_A22") (pintype "passive"))
      (node (ref "X6") (pin "A22") (pinfunction "A22_A22") (pintype "passive"))
      (node (ref "X7") (pin "A22") (pinfunction "A22_A22") (pintype "passive"))
      (node (ref "X8") (pin "A22") (pinfunction "A22_A22") (pintype "passive"))
    )
    (net (code "56") (name "/SIG55") (class "Default")
      (node (ref "X1") (pin "B22") (pinfunction "B22_B22") (pintype "passive"))
      (node (ref "X2") (pin "B22") (pinfunction "B22_B22") (pintype "passive"))
      (node (ref "X3") (pin "B22") (pinfunction "B22_B22") (pintype "passive"))
      (node (ref "X4") (pin "B22") (pinfunction "B22_B22") (pintype "passive"))
      (node (ref "X5") (pin "B22") (pinfunction "B22_B22") (pintype "passive"))
      (node (ref "X6") (pin "B22") (pinfunction "B22_B22") (pintype "passive"))
      (node (ref "X7") (pin "B22") (pinfunction "B22_B22") (pintype "passive"))
      (node (ref "X8") (pin "B22") (pinfunction "B22_B22") (pintype "passive"))
    )
    (net (code "57") (name "/SIG56") (class "Default")
      (node (ref "X1") (pin "C22") (pinfunction "C22_C22") (pintype "passive"))
      (node (ref "X2") (pin "C22") (pinfunction "C22_C22") (pintype "passive"))
      (node (ref "X3") (pin "C22") (pinfunction "C22_C22") (pintype "passive"))
      (node (ref "X4") (pin "C22") (pinfunction "C22_C22") (pintype "passive"))
      (node (ref "X5") (pin "C22") (pinfunction "C22_C22") (pintype "passive"))
      (node (ref "X6") (pin "C22") (pinfunction "C22_C22") (pintype "passive"))
      (node (ref "X7") (pin "C22") (pinfunction "C22_C22") (pintype "passive"))
      (node (ref "X8") (pin "C22") (pinfunction "C22_C22") (pintype "passive"))
    )
    (net (code "58") (name "/SIG57") (class "Default")
      (node (ref "X1") (pin "A23") (pinfunction "A23_A23") (pintype "passive"))
      (node (ref "X2") (pin "A23") (pinfunction "A23_A23") (pintype "passive"))
      (node (ref "X3") (pin "A23") (pinfunction "A23_A23") (pintype "passive"))
      (node (ref "X4") (pin "A23") (pinfunction "A23_A23") (pintype "passive"))
      (node (ref "X5") (pin "A23") (pinfunction "A23_A23") (pintype "passive"))
      (node (ref "X6") (pin "A23") (pinfunction "A23_A23") (pintype "passive"))
      (node (ref "X7") (pin "A23") (pinfunction "A23_A23") (pintype "passive"))
      (node (ref "X8") (pin "A23") (pinfunction "A23_A23") (pintype "passive"))
    )
    (net (code "59") (name "/SIG58") (class "Default")
      (node (ref "X1") (pin "B23") (pinfunction "B23_B23") (pintype "passive"))
      (node (ref "X2") (pin "B23") (pinfunction "B23_B23") (pintype "passive"))
      (node (ref "X3") (pin "B23") (pinfunction "B23_B23") (pintype "passive"))
      (node (ref "X4") (pin "B23") (pinfunction "B23_B23") (pintype "passive"))
      (node (ref "X5") (pin "B23") (pinfunction "B23_B23") (pintype "passive"))
      (node (ref "X6") (pin "B23") (pinfunction "B23_B23") (pintype "passive"))
      (node (ref "X7") (pin "B23") (pinfunction "B23_B23") (pintype "passive"))
      (node (ref "X8") (pin "B23") (pinfunction "B23_B23") (pintype "passive"))
    )
    (net (code "60") (name "/SIG59") (class "Default")
      (node (ref "X1") (pin "C23") (pinfunction "C23_C23") (pintype "passive"))
      (node (ref "X2") (pin "C23") (pinfunction "C23_C23") (pintype "passive"))
      (node (ref "X3") (pin "C23") (pinfunction "C23_C23") (pintype "passive"))
      (node (ref "X4") (pin "C23") (pinfunction "C23_C23") (pintype "passive"))
      (node (ref "X5") (pin "C23") (pinfunction "C23_C23") (pintype "passive"))
      (node (ref "X6") (pin "C23") (pinfunction "C23_C23") (pintype "passive"))
      (node (ref "X7") (pin "C23") (pinfunction "C23_C23") (pintype "passive"))
      (node (ref "X8") (pin "C23") (pinfunction "C23_C23") (pintype "passive"))
    )
    (net (code "61") (name "/SIG60") (class "Default")
      (node (ref "X1") (pin "A24") (pinfunction "A24_A24") (pintype "passive"))
      (node (ref "X2") (pin "A24") (pinfunction "A24_A24") (pintype "passive"))
      (node (ref "X3") (pin "A24") (pinfunction "A24_A24") (pintype "passive"))
      (node (ref "X4") (pin "A24") (pinfunction "A24_A24") (pintype "passive"))
      (node (ref "X5") (pin "A24") (pinfunction "A24_A24") (pintype "passive"))
      (node (ref "X6") (pin "A24") (pinfunction "A24_A24") (pintype "passive"))
      (node (ref "X7") (pin "A24") (pinfunction "A24_A24") (pintype "passive"))
      (node (ref "X8") (pin "A24") (pinfunction "A24_A24") (pintype "passive"))
    )
    (net (code "62") (name "/SIG61") (class "Default")
      (node (ref "X1") (pin "B24") (pinfunction "B24_B24") (pintype "passive"))
      (node (ref "X2") (pin "B24") (pinfunction "B24_B24") (pintype "passive"))
      (node (ref "X3") (pin "B24") (pinfunction "B24_B24") (pintype "passive"))
      (node (ref "X4") (pin "B24") (pinfunction "B24_B24") (pintype "passive"))
      (node (ref "X5") (pin "B24") (pinfunction "B24_B24") (pintype "passive"))
      (node (ref "X6") (pin "B24") (pinfunction "B24_B24") (pintype "passive"))
      (node (ref "X7") (pin "B24") (pinfunction "B24_B24") (pintype "passive"))
      (node (ref "X8") (pin "B24") (pinfunction "B24_B24") (pintype "passive"))
    )
    (net (code "63") (name "/SIG62") (class "Default")
      (node (ref "X1") (pin "C24") (pinfunction "C24_C24") (pintype "passive"))
      (node (ref "X2") (pin "C24") (pinfunction "C24_C24") (pintype "passive"))
      (node (ref "X3") (pin "C24") (pinfunction "C24_C24") (pintype "passive"))
      (node (ref "X4") (pin "C24") (pinfunction "C24_C24") (pintype "passive"))
      (node (ref "X5") (pin "C24") (pinfunction "C24_C24") (pintype "passive"))
      (node (ref "X6") (pin "C24") (pinfunction "C24_C24") (pintype "passive"))
      (node (ref "X7") (pin "C24") (pinfunction "C24_C24") (pintype "passive"))
      (node (ref "X8") (pin "C24") (pinfunction "C24_C24") (pintype "passive"))
    )
    (net (code "64") (name "/SIG63") (class "Default")
      (node (ref "X1") (pin "A25") (pinfunction "A25_A25") (pintype "passive"))
      (node (ref "X2") (pin "A25") (pinfunction "A25_A25") (pintype "passive"))
      (node (ref "X3") (pin "A25") (pinfunction "A25_A25") (pintype "passive"))
      (node (ref "X4") (pin "A25") (pinfunction "A25_A25") (pintype "passive"))
      (node (ref "X5") (pin "A25") (pinfunction "A25_A25") (pintype "passive"))
      (node (ref "X6") (pin "A25") (pinfunction "A25_A25") (pintype "passive"))
      (node (ref "X7") (pin "A25") (pinfunction "A25_A25") (pintype "passive"))
      (node (ref "X8") (pin "A25") (pinfunction "A25_A25") (pintype "passive"))
    )
    (net (code "65") (name "/SIG64") (class "Default")
      (node (ref "X1") (pin "B25") (pinfunction "B25_B25") (pintype "passive"))
      (node (ref "X2") (pin "B25") (pinfunction "B25_B25") (pintype "passive"))
      (node (ref "X3") (pin "B25") (pinfunction "B25_B25") (pintype "passive"))
      (node (ref "X4") (pin "B25") (pinfunction "B25_B25") (pintype "passive"))
      (node (ref "X5") (pin "B25") (pinfunction "B25_B25") (pintype "passive"))
      (node (ref "X6") (pin "B25") (pinfunction "B25_B25") (pintype "passive"))
      (node (ref "X7") (pin "B25") (pinfunction "B25_B25") (pintype "passive"))
      (node (ref "X8") (pin "B25") (pinfunction "B25_B25") (pintype "passive"))
    )
    (net (code "66") (name "/SIG65") (class "Default")
      (node (ref "X1") (pin "C25") (pinfunction "C25_C25") (pintype "passive"))
      (node (ref "X2") (pin "C25") (pinfunction "C25_C25") (pintype "passive"))
      (node (ref "X3") (pin "C25") (pinfunction "C25_C25") (pintype "passive"))
      (node (ref "X4") (pin "C25") (pinfunction "C25_C25") (pintype "passive"))
      (node (ref "X5") (pin "C25") (pinfunction "C25_C25") (pintype "passive"))
      (node (ref "X6") (pin "C25") (pinfunction "C25_C25") (pintype "passive"))
      (node (ref "X7") (pin "C25") (pinfunction "C25_C25") (pintype "passive"))
      (node (ref "X8") (pin "C25") (pinfunction "C25_C25") (pintype "passive"))
    )
    (net (code "67") (name "/SIG66") (class "Default")
      (node (ref "X1") (pin "A26") (pinfunction "A26_A26") (pintype "passive"))
      (node (ref "X2") (pin "A26") (pinfunction "A26_A26") (pintype "passive"))
      (node (ref "X3") (pin "A26") (pinfunction "A26_A26") (pintype "passive"))
      (node (ref "X4") (pin "A26") (pinfunction "A26_A26") (pintype "passive"))
      (node (ref "X5") (pin "A26") (pinfunction "A26_A26") (pintype "passive"))
      (node (ref "X6") (pin "A26") (pinfunction "A26_A26") (pintype "passive"))
      (node (ref "X7") (pin "A26") (pinfunction "A26_A26") (pintype "passive"))
      (node (ref "X8") (pin "A26") (pinfunction "A26_A26") (pintype "passive"))
    )
    (net (code "68") (name "/SIG67") (class "Default")
      (node (ref "X1") (pin "B26") (pinfunction "B26_B26") (pintype "passive"))
      (node (ref "X2") (pin "B26") (pinfunction "B26_B26") (pintype "passive"))
      (node (ref "X3") (pin "B26") (pinfunction "B26_B26") (pintype "passive"))
      (node (ref "X4") (pin "B26") (pinfunction "B26_B26") (pintype "passive"))
      (node (ref "X5") (pin "B26") (pinfunction "B26_B26") (pintype "passive"))
      (node (ref "X6") (pin "B26") (pinfunction "B26_B26") (pintype "passive"))
      (node (ref "X7") (pin "B26") (pinfunction "B26_B26") (pintype "passive"))
      (node (ref "X8") (pin "B26") (pinfunction "B26_B26") (pintype "passive"))
    )
    (net (code "69") (name "/SIG68") (class "Default")
      (node (ref "X1") (pin "C26") (pinfunction "C26_C26") (pintype "passive"))
      (node (ref "X2") (pin "C26") (pinfunction "C26_C26") (pintype "passive"))
      (node (ref "X3") (pin "C26") (pinfunction "C26_C26") (pintype "passive"))
      (node (ref "X4") (pin "C26") (pinfunction "C26_C26") (pintype "passive"))
      (node (ref "X5") (pin "C26") (pinfunction "C26_C26") (pintype "passive"))
      (node (ref "X6") (pin "C26") (pinfunction "C26_C26") (pintype "passive"))
      (node (ref "X7") (pin "C26") (pinfunction "C26_C26") (pintype "passive"))
      (node (ref "X8") (pin "C26") (pinfunction "C26_C26") (pintype "passive"))
    )
    (net (code "70") (name "/SIG69") (class "Default")
      (node (ref "X1") (pin "A27") (pinfunction "A27_A27") (pintype "passive"))
      (node (ref "X2") (pin "A27") (pinfunction "A27_A27") (pintype "passive"))
      (node (ref "X3") (pin "A27") (pinfunction "A27_A27") (pintype "passive"))
      (node (ref "X4") (pin "A27") (pinfunction "A27_A27") (pintype "passive"))
      (node (ref "X5") (pin "A27") (pinfunction "A27_A27") (pintype "passive"))
      (node (ref "X6") (pin "A27") (pinfunction "A27_A27") (pintype "passive"))
      (node (ref "X7") (pin "A27") (pinfunction "A27_A27") (pintype "passive"))
      (node (ref "X8") (pin "A27") (pinfunction "A27_A27") (pintype "passive"))
    )
    (net (code "71") (name "/SIG70") (class "Default")
      (node (ref "X1") (pin "B27") (pinfunction "B27_B27") (pintype "passive"))
      (node (ref "X2") (pin "B27") (pinfunction "B27_B27") (pintype "passive"))
      (node (ref "X3") (pin "B27") (pinfunction "B27_B27") (pintype "passive"))
      (node (ref "X4") (pin "B27") (pinfunction "B27_B27") (pintype "passive"))
      (node (ref "X5") (pin "B27") (pinfunction "B27_B27") (pintype "passive"))
      (node (ref "X6") (pin "B27") (pinfunction "B27_B27") (pintype "passive"))
      (node (ref "X7") (pin "B27") (pinfunction "B27_B27") (pintype "passive"))
      (node (ref "X8") (pin "B27") (pinfunction "B27_B27") (pintype "passive"))
    )
    (net (code "72") (name "/SIG71") (class "Default")
      (node (ref "X1") (pin "C27") (pinfunction "C27_C27") (pintype "passive"))
      (node (ref "X2") (pin "C27") (pinfunction "C27_C27") (pintype "passive"))
      (node (ref "X3") (pin "C27") (pinfunction "C27_C27") (pintype "passive"))
      (node (ref "X4") (pin "C27") (pinfunction "C27_C27") (pintype "passive"))
      (node (ref "X5") (pin "C27") (pinfunction "C27_C27") (pintype "passive"))
      (node (ref "X6") (pin "C27") (pinfunction "C27_C27") (pintype "passive"))
      (node (ref "X7") (pin "C27") (pinfunction "C27_C27") (pintype "passive"))
      (node (ref "X8") (pin "C27") (pinfunction "C27_C27") (pintype "passive"))
    )
    (net (code "73") (name "/SIG72") (class "Default")
      (node (ref "X1") (pin "A28") (pinfunction "A28_A28") (pintype "passive"))
      (node (ref "X2") (pin "A28") (pinfunction "A28_A28") (pintype "passive"))
      (node (ref "X3") (pin "A28") (pinfunction "A28_A28") (pintype "passive"))
      (node (ref "X4") (pin "A28") (pinfunction "A28_A28") (pintype "passive"))
      (node (ref "X5") (pin "A28") (pinfunction "A28_A28") (pintype "passive"))
      (node (ref "X6") (pin "A28") (pinfunction "A28_A28") (pintype "passive"))
      (node (ref "X7") (pin "A28") (pinfunction "A28_A28") (pintype "passive"))
      (node (ref "X8") (pin "A28") (pinfunction "A28_A28") (pintype "passive"))
    )
    (net (code "74") (name "/SIG73") (class "Default")
      (node (ref "X1") (pin "B28") (pinfunction "B28_B28") (pintype "passive"))
      (node (ref "X2") (pin "B28") (pinfunction "B28_B28") (pintype "passive"))
      (node (ref "X3") (pin "B28") (pinfunction "B28_B28") (pintype "passive"))
      (node (ref "X4") (pin "B28") (pinfunction "B28_B28") (pintype "passive"))
      (node (ref "X5") (pin "B28") (pinfunction "B28_B28") (pintype "passive"))
      (node (ref "X6") (pin "B28") (pinfunction "B28_B28") (pintype "passive"))
      (node (ref "X7") (pin "B28") (pinfunction "B28_B28") (pintype "passive"))
      (node (ref "X8") (pin "B28") (pinfunction "B28_B28") (pintype "passive"))
    )
    (net (code "75") (name "/SIG74") (class "Default")
      (node (ref "X1") (pin "C28") (pinfunction "C28_C28") (pintype "passive"))
      (node (ref "X2") (pin "C28") (pinfunction "C28_C28") (pintype "passive"))
      (node (ref "X3") (pin "C28") (pinfunction "C28_C28") (pintype "passive"))
      (node (ref "X4") (pin "C28") (pinfunction "C28_C28") (pintype "passive"))
      (node (ref "X5") (pin "C28") (pinfunction "C28_C28") (pintype "passive"))
      (node (ref "X6") (pin "C28") (pinfunction "C28_C28") (pintype "passive"))
      (node (ref "X7") (pin "C28") (pinfunction "C28_C28") (pintype "passive"))
      (node (ref "X8") (pin "C28") (pinfunction "C28_C28") (pintype "passive"))
    )
    (net (code "76") (name "/SIG75") (class "Default")
      (node (ref "X1") (pin "A29") (pinfunction "A29_A29") (pintype "passive"))
      (node (ref "X2") (pin "A29") (pinfunction "A29_A29") (pintype "passive"))
      (node (ref "X3") (pin "A29") (pinfunction "A29_A29") (pintype "passive"))
      (node (ref "X4") (pin "A29") (pinfunction "A29_A29") (pintype "passive"))
      (node (ref "X5") (pin "A29") (pinfunction "A29_A29") (pintype "passive"))
      (node (ref "X6") (pin "A29") (pinfunction "A29_A29") (pintype "passive"))
      (node (ref "X7") (pin "A29") (pinfunction "A29_A29") (pintype "passive"))
      (node (ref "X8") (pin "A29") (pinfunction "A29_A29") (pintype "passive"))
    )
    (net (code "77") (name "/SIG76") (class "Default")
      (node (ref "X1") (pin "B29") (pinfunction "B29_B29") (pintype "passive"))
      (node (ref "X2") (pin "B29") (pinfunction "B29_B29") (pintype "passive"))
      (node (ref "X3") (pin "B29") (pinfunction "B29_B29") (pintype "passive"))
      (node (ref "X4") (pin "B29") (pinfunction "B29_B29") (pintype "passive"))
      (node (ref "X5") (pin "B29") (pinfunction "B29_B29") (pintype "passive"))
      (node (ref "X6") (pin "B29") (pinfunction "B29_B29") (pintype "passive"))
      (node (ref "X7") (pin "B29") (pinfunction "B29_B29") (pintype "passive"))
      (node (ref "X8") (pin "B29") (pinfunction "B29_B29") (pintype "passive"))
    )
    (net (code "78") (name "/SIG77") (class "Default")
      (node (ref "X1") (pin "C29") (pinfunction "C29_C29") (pintype "passive"))
      (node (ref "X2") (pin "C29") (pinfunction "C29_C29") (pintype "passive"))
      (node (ref "X3") (pin "C29") (pinfunction "C29_C29") (pintype "passive"))
      (node (ref "X4") (pin "C29") (pinfunction "C29_C29") (pintype "passive"))
      (node (ref "X5") (pin "C29") (pinfunction "C29_C29") (pintype "passive"))
      (node (ref "X6") (pin "C29") (pinfunction "C29_C29") (pintype "passive"))
      (node (ref "X7") (pin "C29") (pinfunction "C29_C29") (pintype "passive"))
      (node (ref "X8") (pin "C29") (pinfunction "C29_C29") (pintype "passive"))
    )
    (net (code "79") (name "/SIG78") (class "Default")
      (node (ref "X1") (pin "A30") (pinfunction "A30_A30") (pintype "passive"))
      (node (ref "X2") (pin "A30") (pinfunction "A30_A30") (pintype "passive"))
      (node (ref "X3") (pin "A30") (pinfunction "A30_A30") (pintype "passive"))
      (node (ref "X4") (pin "A30") (pinfunction "A30_A30") (pintype "passive"))
      (node (ref "X5") (pin "A30") (pinfunction "A30_A30") (pintype "passive"))
      (node (ref "X6") (pin "A30") (pinfunction "A30_A30") (pintype "passive"))
      (node (ref "X7") (pin "A30") (pinfunction "A30_A30") (pintype "passive"))
      (node (ref "X8") (pin "A30") (pinfunction "A30_A30") (pintype "passive"))
    )
    (net (code "80") (name "/SIG79") (class "Default")
      (node (ref "X1") (pin "B30") (pinfunction "B30_B30") (pintype "passive"))
      (node (ref "X2") (pin "B30") (pinfunction "B30_B30") (pintype "passive"))
      (node (ref "X3") (pin "B30") (pinfunction "B30_B30") (pintype "passive"))
      (node (ref "X4") (pin "B30") (pinfunction "B30_B30") (pintype "passive"))
      (node (ref "X5") (pin "B30") (pinfunction "B30_B30") (pintype "passive"))
      (node (ref "X6") (pin "B30") (pinfunction "B30_B30") (pintype "passive"))
      (node (ref "X7") (pin "B30") (pinfunction "B30_B30") (pintype "passive"))
      (node (ref "X8") (pin "B30") (pinfunction "B30_B30") (pintype "passive"))
    )
    (net (code "81") (name "/SIG80") (class "Default")
      (node (ref "X1") (pin "C30") (pinfunction "C30_C30") (pintype "passive"))
      (node (ref "X2") (pin "C30") (pinfunction "C30_C30") (pintype "passive"))
      (node (ref "X3") (pin "C30") (pinfunction "C30_C30") (pintype "passive"))
      (node (ref "X4") (pin "C30") (pinfunction "C30_C30") (pintype "passive"))
      (node (ref "X5") (pin "C30") (pinfunction "C30_C30") (pintype "passive"))
      (node (ref "X6") (pin "C30") (pinfunction "C30_C30") (pintype "passive"))
      (node (ref "X7") (pin "C30") (pinfunction "C30_C30") (pintype "passive"))
      (node (ref "X8") (pin "C30") (pinfunction "C30_C30") (pintype "passive"))
    )
    (net (code "82") (name "/SIG81") (class "Default")
      (node (ref "X1") (pin "A3") (pinfunction "A3_A3") (pintype "passive"))
      (node (ref "X2") (pin "A3") (pinfunction "A3_A3") (pintype "passive"))
      (node (ref "X3") (pin "A3") (pinfunction "A3_A3") (pintype "passive"))
      (node (ref "X4") (pin "A3") (pinfunction "A3_A3") (pintype "passive"))
      (node (ref "X5") (pin "A3") (pinfunction "A3_A3") (pintype "passive"))
      (node (ref "X6") (pin "A3") (pinfunction "A3_A3") (pintype "passive"))
      (node (ref "X7") (pin "A3") (pinfunction "A3_A3") (pintype "passive"))
      (node (ref "X8") (pin "A3") (pinfunction "A3_A3") (pintype "passive"))
    )
    (net (code "83") (name "/SIG82") (class "Default")
      (node (ref "X1") (pin "B3") (pinfunction "B3_B3") (pintype "passive"))
      (node (ref "X2") (pin "B3") (pinfunction "B3_B3") (pintype "passive"))
      (node (ref "X3") (pin "B3") (pinfunction "B3_B3") (pintype "passive"))
      (node (ref "X4") (pin "B3") (pinfunction "B3_B3") (pintype "passive"))
      (node (ref "X5") (pin "B3") (pinfunction "B3_B3") (pintype "passive"))
      (node (ref "X6") (pin "B3") (pinfunction "B3_B3") (pintype "passive"))
      (node (ref "X7") (pin "B3") (pinfunction "B3_B3") (pintype "passive"))
      (node (ref "X8") (pin "B3") (pinfunction "B3_B3") (pintype "passive"))
    )
    (net (code "84") (name "/SIG83") (class "Default")
      (node (ref "X1") (pin "C3") (pinfunction "C3_C3") (pintype "passive"))
      (node (ref "X2") (pin "C3") (pinfunction "C3_C3") (pintype "passive"))
      (node (ref "X3") (pin "C3") (pinfunction "C3_C3") (pintype "passive"))
      (node (ref "X4") (pin "C3") (pinfunction "C3_C3") (pintype "passive"))
      (node (ref "X5") (pin "C3") (pinfunction "C3_C3") (pintype "passive"))
      (node (ref "X6") (pin "C3") (pinfunction "C3_C3") (pintype "passive"))
      (node (ref "X7") (pin "C3") (pinfunction "C3_C3") (pintype "passive"))
      (node (ref "X8") (pin "C3") (pinfunction "C3_C3") (pintype "passive"))
    )
    (net (code "85") (name "5V") (class "Default")
      (node (ref "5V") (pin "1") (pinfunction "P_1") (pintype "passive"))
      (node (ref "C1") (pin "+") (pinfunction "+_+") (pintype "passive"))
      (node (ref "C2") (pin "+") (pinfunction "+_+") (pintype "passive"))
      (node (ref "C3") (pin "+") (pinfunction "+_+") (pintype "passive"))
      (node (ref "C4") (pin "+") (pinfunction "+_+") (pintype "passive"))
      (node (ref "C5") (pin "+") (pinfunction "+_+") (pintype "passive"))
      (node (ref "C6") (pin "+") (pinfunction "+_+") (pintype "passive"))
      (node (ref "C7") (pin "+") (pinfunction "+_+") (pintype "passive"))
      (node (ref "C8") (pin "+") (pinfunction "+_+") (pintype "passive"))
      (node (ref "R1") (pin "2") (pinfunction "2_2") (pintype "passive"))
      (node (ref "X1") (pin "A2") (pinfunction "A2_A2") (pintype "passive"))
      (node (ref "X1") (pin "A31") (pinfunction "A31_A31") (pintype "passive"))
      (node (ref "X1") (pin "B2") (pinfunction "B2_B2") (pintype "passive"))
      (node (ref "X1") (pin "B31") (pinfunction "B31_B31") (pintype "passive"))
      (node (ref "X1") (pin "C2") (pinfunction "C2_C2") (pintype "passive"))
      (node (ref "X1") (pin "C31") (pinfunction "C31_C31") (pintype "passive"))
      (node (ref "X2") (pin "A2") (pinfunction "A2_A2") (pintype "passive"))
      (node (ref "X2") (pin "A31") (pinfunction "A31_A31") (pintype "passive"))
      (node (ref "X2") (pin "B2") (pinfunction "B2_B2") (pintype "passive"))
      (node (ref "X2") (pin "B31") (pinfunction "B31_B31") (pintype "passive"))
      (node (ref "X2") (pin "C2") (pinfunction "C2_C2") (pintype "passive"))
      (node (ref "X2") (pin "C31") (pinfunction "C31_C31") (pintype "passive"))
      (node (ref "X3") (pin "A2") (pinfunction "A2_A2") (pintype "passive"))
      (node (ref "X3") (pin "A31") (pinfunction "A31_A31") (pintype "passive"))
      (node (ref "X3") (pin "B2") (pinfunction "B2_B2") (pintype "passive"))
      (node (ref "X3") (pin "B31") (pinfunction "B31_B31") (pintype "passive"))
      (node (ref "X3") (pin "C2") (pinfunction "C2_C2") (pintype "passive"))
      (node (ref "X3") (pin "C31") (pinfunction "C31_C31") (pintype "passive"))
      (node (ref "X4") (pin "A2") (pinfunction "A2_A2") (pintype "passive"))
      (node (ref "X4") (pin "A31") (pinfunction "A31_A31") (pintype "passive"))
      (node (ref "X4") (pin "B2") (pinfunction "B2_B2") (pintype "passive"))
      (node (ref "X4") (pin "B31") (pinfunction "B31_B31") (pintype "passive"))
      (node (ref "X4") (pin "C2") (pinfunction "C2_C2") (pintype "passive"))
      (node (ref "X4") (pin "C31") (pinfunction "C31_C31") (pintype "passive"))
      (node (ref "X5") (pin "A2") (pinfunction "A2_A2") (pintype "passive"))
      (node (ref "X5") (pin "A31") (pinfunction "A31_A31") (pintype "passive"))
      (node (ref "X5") (pin "B2") (pinfunction "B2_B2") (pintype "passive"))
      (node (ref "X5") (pin "B31") (pinfunction "B31_B31") (pintype "passive"))
      (node (ref "X5") (pin "C2") (pinfunction "C2_C2") (pintype "passive"))
      (node (ref "X5") (pin "C31") (pinfunction "C31_C31") (pintype "passive"))
      (node (ref "X6") (pin "A2") (pinfunction "A2_A2") (pintype "passive"))
      (node (ref "X6") (pin "A31") (pinfunction "A31_A31") (pintype "passive"))
      (node (ref "X6") (pin "B2") (pinfunction "B2_B2") (pintype "passive"))
      (node (ref "X6") (pin "B31") (pinfunction "B31_B31") (pintype "passive"))
      (node (ref "X6") (pin "C2") (pinfunction "C2_C2") (pintype "passive"))
      (node (ref "X6") (pin "C31") (pinfunction "C31_C31") (pintype "passive"))
      (node (ref "X7") (pin "A2") (pinfunction "A2_A2") (pintype "passive"))
      (node (ref "X7") (pin "A31") (pinfunction "A31_A31") (pintype "passive"))
      (node (ref "X7") (pin "B2") (pinfunction "B2_B2") (pintype "passive"))
      (node (ref "X7") (pin "B31") (pinfunction "B31_B31") (pintype "passive"))
      (node (ref "X7") (pin "C2") (pinfunction "C2_C2") (pintype "passive"))
      (node (ref "X7") (pin "C31") (pinfunction "C31_C31") (pintype "passive"))
      (node (ref "X8") (pin "A2") (pinfunction "A2_A2") (pintype "passive"))
      (node (ref "X8") (pin "A31") (pinfunction "A31_A31") (pintype "passive"))
      (node (ref "X8") (pin "B2") (pinfunction "B2_B2") (pintype "passive"))
      (node (ref "X8") (pin "B31") (pinfunction "B31_B31") (pintype "passive"))
      (node (ref "X8") (pin "C2") (pinfunction "C2_C2") (pintype "passive"))
      (node (ref "X8") (pin "C31") (pinfunction "C31_C31") (pintype "passive"))
    )
    (net (code "86") (name "GND") (class "Default")
      (node (ref "C1") (pin "-") (pinfunction "-_-") (pintype "passive"))
      (node (ref "C2") (pin "-") (pinfunction "-_-") (pintype "passive"))
      (node (ref "C3") (pin "-") (pinfunction "-_-") (pintype "passive"))
      (node (ref "C4") (pin "-") (pinfunction "-_-") (pintype "passive"))
      (node (ref "C5") (pin "-") (pinfunction "-_-") (pintype "passive"))
      (node (ref "C6") (pin "-") (pinfunction "-_-") (pintype "passive"))
      (node (ref "C7") (pin "-") (pinfunction "-_-") (pintype "passive"))
      (node (ref "C8") (pin "-") (pinfunction "-_-") (pintype "passive"))
      (node (ref "GND") (pin "1") (pinfunction "P_1") (pintype "passive"))
      (node (ref "PWR") (pin "K") (pinfunction "C_K") (pintype "passive"))
      (node (ref "X1") (pin "A1") (pinfunction "A1_A1") (pintype "passive"))
      (node (ref "X1") (pin "A32") (pinfunction "A32_A32") (pintype "passive"))
      (node (ref "X1") (pin "B1") (pinfunction "B1_B1") (pintype "passive"))
      (node (ref "X1") (pin "B32") (pinfunction "B32_B32") (pintype "passive"))
      (node (ref "X1") (pin "C1") (pinfunction "C1_C1") (pintype "passive"))
      (node (ref "X1") (pin "C32") (pinfunction "C32_C32") (pintype "passive"))
      (node (ref "X2") (pin "A1") (pinfunction "A1_A1") (pintype "passive"))
      (node (ref "X2") (pin "A32") (pinfunction "A32_A32") (pintype "passive"))
      (node (ref "X2") (pin "B1") (pinfunction "B1_B1") (pintype "passive"))
      (node (ref "X2") (pin "B32") (pinfunction "B32_B32") (pintype "passive"))
      (node (ref "X2") (pin "C1") (pinfunction "C1_C1") (pintype "passive"))
      (node (ref "X2") (pin "C32") (pinfunction "C32_C32") (pintype "passive"))
      (node (ref "X3") (pin "A1") (pinfunction "A1_A1") (pintype "passive"))
      (node (ref "X3") (pin "A32") (pinfunction "A32_A32") (pintype "passive"))
      (node (ref "X3") (pin "B1") (pinfunction "B1_B1") (pintype "passive"))
      (node (ref "X3") (pin "B32") (pinfunction "B32_B32") (pintype "passive"))
      (node (ref "X3") (pin "C1") (pinfunction "C1_C1") (pintype "passive"))
      (node (ref "X3") (pin "C32") (pinfunction "C32_C32") (pintype "passive"))
      (node (ref "X4") (pin "A1") (pinfunction "A1_A1") (pintype "passive"))
      (node (ref "X4") (pin "A32") (pinfunction "A32_A32") (pintype "passive"))
      (node (ref "X4") (pin "B1") (pinfunction "B1_B1") (pintype "passive"))
      (node (ref "X4") (pin "B32") (pinfunction "B32_B32") (pintype "passive"))
      (node (ref "X4") (pin "C1") (pinfunction "C1_C1") (pintype "passive"))
      (node (ref "X4") (pin "C32") (pinfunction "C32_C32") (pintype "passive"))
      (node (ref "X5") (pin "A1") (pinfunction "A1_A1") (pintype "passive"))
      (node (ref "X5") (pin "A32") (pinfunction "A32_A32") (pintype "passive"))
      (node (ref "X5") (pin "B1") (pinfunction "B1_B1") (pintype "passive"))
      (node (ref "X5") (pin "B32") (pinfunction "B32_B32") (pintype "passive"))
      (node (ref "X5") (pin "C1") (pinfunction "C1_C1") (pintype "passive"))
      (node (ref "X5") (pin "C32") (pinfunction "C32_C32") (pintype "passive"))
      (node (ref "X6") (pin "A1") (pinfunction "A1_A1") (pintype "passive"))
      (node (ref "X6") (pin "A32") (pinfunction "A32_A32") (pintype "passive"))
      (node (ref "X6") (pin "B1") (pinfunction "B1_B1") (pintype "passive"))
      (node (ref "X6") (pin "B32") (pinfunction "B32_B32") (pintype "passive"))
      (node (ref "X6") (pin "C1") (pinfunction "C1_C1") (pintype "passive"))
      (node (ref "X6") (pin "C32") (pinfunction "C32_C32") (pintype "passive"))
      (node (ref "X7") (pin "A1") (pinfunction "A1_A1") (pintype "passive"))
      (node (ref "X7") (pin "A32") (pinfunction "A32_A32") (pintype "passive"))
      (node (ref "X7") (pin "B1") (pinfunction "B1_B1") (pintype "passive"))
      (node (ref "X7") (pin "B32") (pinfunction "B32_B32") (pintype "passive"))
      (node (ref "X7") (pin "C1") (pinfunction "C1_C1") (pintype "passive"))
      (node (ref "X7") (pin "C32") (pinfunction "C32_C32") (pintype "passive"))
      (node (ref "X8") (pin "A1") (pinfunction "A1_A1") (pintype "passive"))
      (node (ref "X8") (pin "A32") (pinfunction "A32_A32") (pintype "passive"))
      (node (ref "X8") (pin "B1") (pinfunction "B1_B1") (pintype "passive"))
      (node (ref "X8") (pin "B32") (pinfunction "B32_B32") (pintype "passive"))
      (node (ref "X8") (pin "C1") (pinfunction "C1_C1") (pintype "passive"))
      (node (ref "X8") (pin "C32") (pinfunction "C32_C32") (pintype "passive"))
    )
    (net (code "87") (name "Net-(PWR-PadA)") (class "Default")
      (node (ref "PWR") (pin "A") (pinfunction "A_A") (pintype "passive"))
      (node (ref "R1") (pin "1") (pinfunction "1_1") (pintype "passive"))
    )
  )
)
